# SCHEMATIC.net
KiCad netlist of a schematic drawn in EAGLE
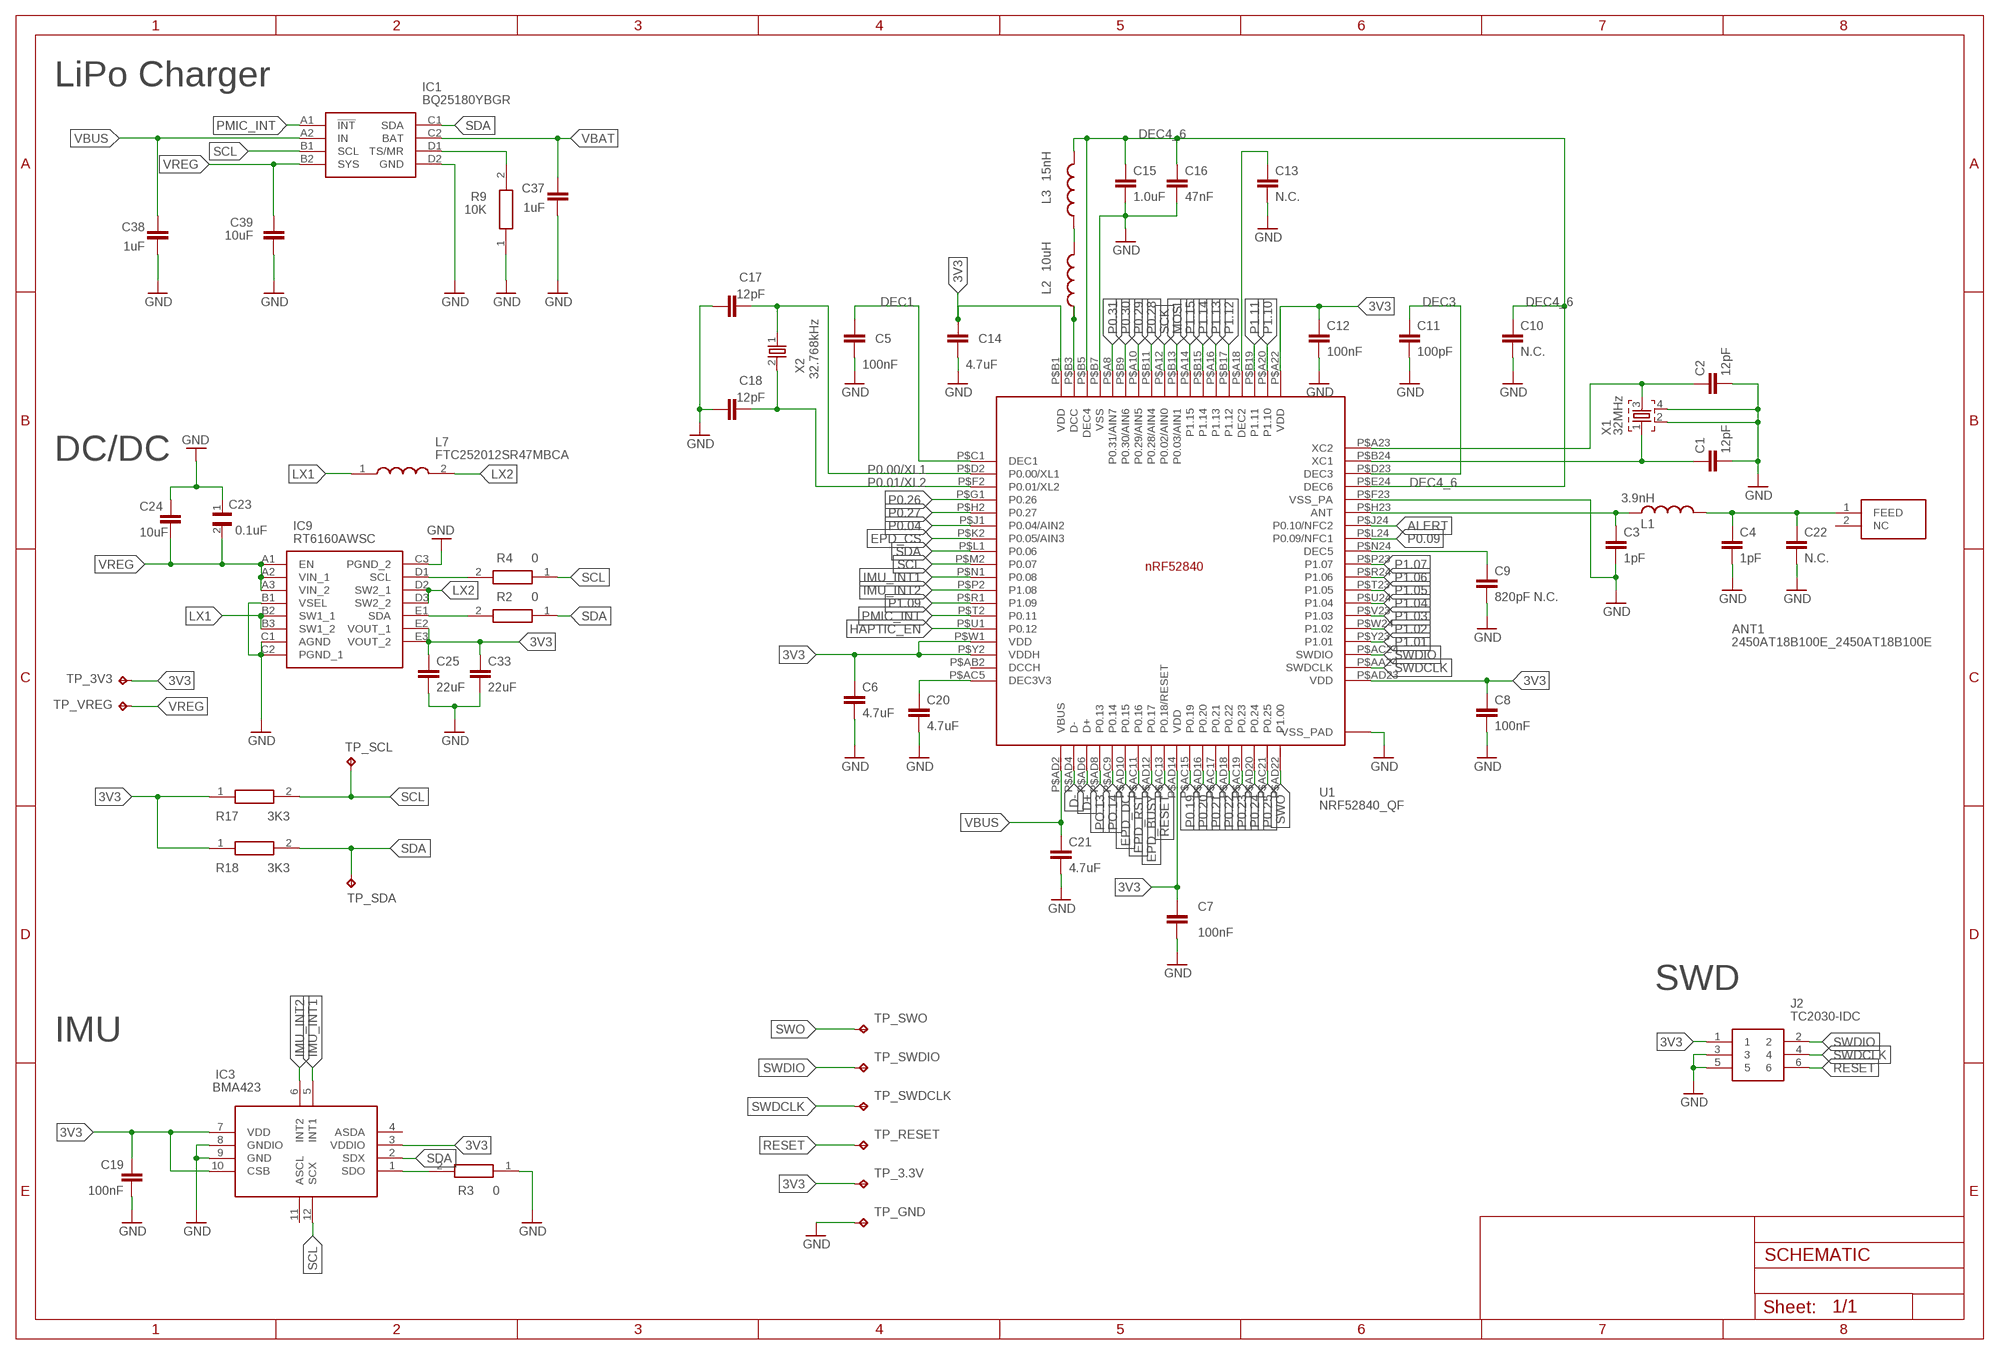
[diagram p0: schematic, sheet 1, part 1 of 2]
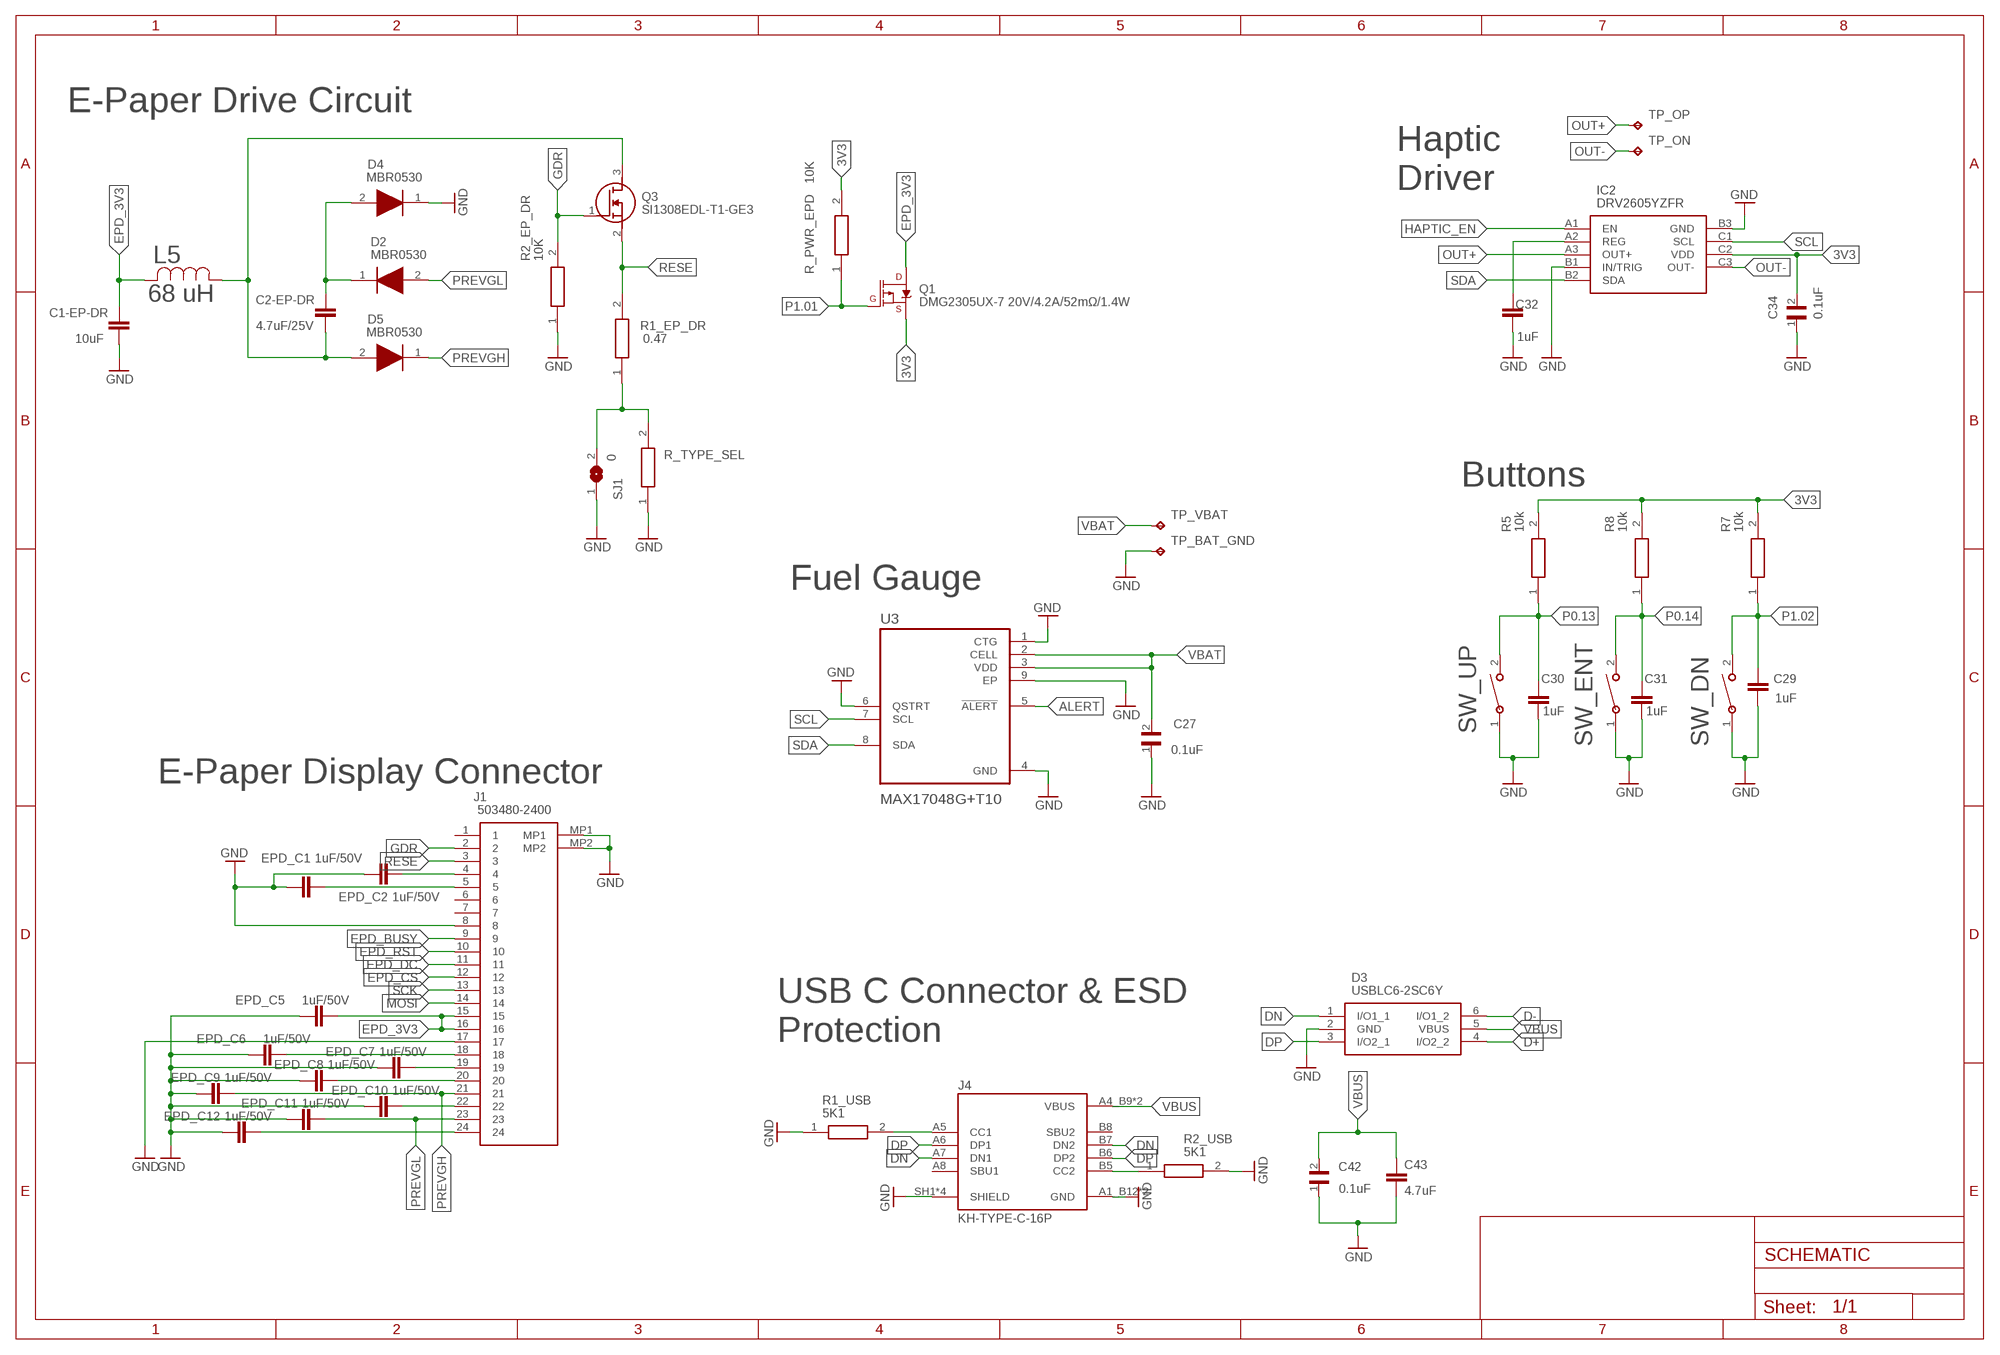
[diagram p1: schematic, sheet 1, part 2 of 2]

(export (version "E")
  (design (tool "Eeschema 10.0.6"))
  (components
    (comp (ref "ANT1")
      (value "2450AT18B100E_2450AT18B100E")
      (footprint "eagle-import:2450AT18B100E_ANTC3216X140N")
      (fields
        (field (name "ARROW_PART_NUMBER") "2450AT18B100E")
        (field (name "MOUSER_PART_NUMBER") "609-2450AT18B100E")
      )
      (libsource (lib "eagle-import") (part "2450AT18B100E_2450AT18B100E"))
    )
    (comp (ref "C1")
      (value "12pF")
      (footprint "eagle-import:NORDIC_NRF_3_RESC0201_L")
      (libsource (lib "eagle-import") (part "NORDIC_NRF_3_CAPACITOR_0201_L"))
    )
    (comp (ref "C1-EP-DR")
      (value "10uF")
      (footprint "eagle-import:PERFECT_0402_0402")
      (libsource (lib "eagle-import") (part "PERFECT_0402_CAP_0402"))
    )
    (comp (ref "C2")
      (value "12pF")
      (footprint "eagle-import:NORDIC_NRF_3_RESC0201_L")
      (libsource (lib "eagle-import") (part "NORDIC_NRF_3_CAPACITOR_0201_L"))
    )
    (comp (ref "C2-EP-DR")
      (value "4.7uF/25V")
      (footprint "eagle-import:PERFECT_0402_0402")
      (libsource (lib "eagle-import") (part "PERFECT_0402_CAP_0402"))
    )
    (comp (ref "C3")
      (value "1pF")
      (footprint "eagle-import:NORDIC_NRF_3_RESC0201_L")
      (libsource (lib "eagle-import") (part "NORDIC_NRF_3_CAPACITOR_0201_L"))
    )
    (comp (ref "C4")
      (value "1pF")
      (footprint "eagle-import:NORDIC_NRF_3_RESC0201_L")
      (libsource (lib "eagle-import") (part "NORDIC_NRF_3_CAPACITOR_0201_L"))
    )
    (comp (ref "C5")
      (value "100nF")
      (footprint "eagle-import:NORDIC_NRF_3_RESC0201_L")
      (libsource (lib "eagle-import") (part "NORDIC_NRF_3_CAPACITOR_0201_L"))
    )
    (comp (ref "C6")
      (value "4.7uF")
      (footprint "eagle-import:PERFECT_0402_0402")
      (libsource (lib "eagle-import") (part "PERFECT_0402_CAP_0402"))
    )
    (comp (ref "C7")
      (value "100nF")
      (footprint "eagle-import:NORDIC_NRF_3_RESC0201_L")
      (libsource (lib "eagle-import") (part "NORDIC_NRF_3_CAPACITOR_0201_L"))
    )
    (comp (ref "C8")
      (value "100nF")
      (footprint "eagle-import:NORDIC_NRF_3_RESC0201_L")
      (libsource (lib "eagle-import") (part "NORDIC_NRF_3_CAPACITOR_0201_L"))
    )
    (comp (ref "C9")
      (value "820pF N.C.")
      (footprint "eagle-import:NORDIC_NRF_3_RESC0201_L")
      (libsource (lib "eagle-import") (part "NORDIC_NRF_3_CAPACITOR_0201_L"))
    )
    (comp (ref "C10")
      (value "N.C.")
      (footprint "eagle-import:NORDIC_NRF_3_RESC0201_L")
      (libsource (lib "eagle-import") (part "NORDIC_NRF_3_CAPACITOR_0201_L"))
    )
    (comp (ref "C11")
      (value "100pF")
      (footprint "eagle-import:NORDIC_NRF_3_RESC0201_L")
      (libsource (lib "eagle-import") (part "NORDIC_NRF_3_CAPACITOR_0201_L"))
    )
    (comp (ref "C12")
      (value "100nF")
      (footprint "eagle-import:NORDIC_NRF_3_RESC0201_L")
      (libsource (lib "eagle-import") (part "NORDIC_NRF_3_CAPACITOR_0201_L"))
    )
    (comp (ref "C13")
      (value "N.C.")
      (footprint "eagle-import:NORDIC_NRF_3_RESC0201_L")
      (libsource (lib "eagle-import") (part "NORDIC_NRF_3_CAPACITOR_0201_L"))
    )
    (comp (ref "C14")
      (value "4.7uF")
      (footprint "eagle-import:PERFECT_0402_0402")
      (libsource (lib "eagle-import") (part "PERFECT_0402_CAP_0402"))
    )
    (comp (ref "C15")
      (value "1.0uF")
      (footprint "eagle-import:PERFECT_0402_0402")
      (libsource (lib "eagle-import") (part "PERFECT_0402_CAP_0402"))
    )
    (comp (ref "C16")
      (value "47nF")
      (footprint "eagle-import:NORDIC_NRF_3_RESC0201_L")
      (libsource (lib "eagle-import") (part "NORDIC_NRF_3_CAPACITOR_0201_L"))
    )
    (comp (ref "C17")
      (value "12pF")
      (footprint "eagle-import:NORDIC_NRF_3_RESC0201_L")
      (libsource (lib "eagle-import") (part "NORDIC_NRF_3_CAPACITOR_0201_L"))
    )
    (comp (ref "C18")
      (value "12pF")
      (footprint "eagle-import:NORDIC_NRF_3_RESC0201_L")
      (libsource (lib "eagle-import") (part "NORDIC_NRF_3_CAPACITOR_0201_L"))
    )
    (comp (ref "C19")
      (value "100nF")
      (footprint "eagle-import:NORDIC_NRF_3_RESC0201_L")
      (libsource (lib "eagle-import") (part "NORDIC_NRF_3_CAPACITOR_0201_L"))
    )
    (comp (ref "C20")
      (value "4.7uF")
      (footprint "eagle-import:PERFECT_0402_0402")
      (libsource (lib "eagle-import") (part "PERFECT_0402_CAP_0402"))
    )
    (comp (ref "C21")
      (value "4.7uF")
      (footprint "eagle-import:PERFECT_0402_0402")
      (libsource (lib "eagle-import") (part "PERFECT_0402_CAP_0402"))
    )
    (comp (ref "C22")
      (value "N.C.")
      (footprint "eagle-import:NORDIC_NRF_3_RESC0201_L")
      (libsource (lib "eagle-import") (part "NORDIC_NRF_3_CAPACITOR_0201_L"))
    )
    (comp (ref "C23")
      (value "0.1uF")
      (footprint "eagle-import:GRM011R60J152KE01L_1_0201")
      (libsource (lib "eagle-import") (part "GRM011R60J152KE01L_1_GRM011R60J152KE01L"))
    )
    (comp (ref "C24")
      (value "10uF")
      (footprint "eagle-import:PERFECT_0402_0402")
      (libsource (lib "eagle-import") (part "PERFECT_0402_CAP_0402"))
    )
    (comp (ref "C25")
      (value "22uF")
      (footprint "eagle-import:PERFECT_0402_0402")
      (libsource (lib "eagle-import") (part "PERFECT_0402_CAP_0402"))
    )
    (comp (ref "C27")
      (value "0.1uF")
      (footprint "eagle-import:GRM011R60J152KE01L_2_CAPC0201X13N")
      (fields (field (name "MF") "Murata") (field (name "MP") "GRM011R60J152KE01L"))
      (libsource (lib "eagle-import") (part "GRM011R60J152KE01L_2_GRM011R60J152KE01L"))
    )
    (comp (ref "C29")
      (value "1uF")
      (footprint "eagle-import:NORDIC_NRF_3_RESC0402_L")
      (libsource (lib "eagle-import") (part "NORDIC_NRF_3_CAPACITOR_0402_L"))
    )
    (comp (ref "C30")
      (value "1uF")
      (footprint "eagle-import:NORDIC_NRF_3_RESC0402_L")
      (libsource (lib "eagle-import") (part "NORDIC_NRF_3_CAPACITOR_0402_L"))
    )
    (comp (ref "C31")
      (value "1uF")
      (footprint "eagle-import:NORDIC_NRF_3_RESC0402_L")
      (libsource (lib "eagle-import") (part "NORDIC_NRF_3_CAPACITOR_0402_L"))
    )
    (comp (ref "C32")
      (value "1uF")
      (footprint "eagle-import:NORDIC_NRF_3_RESC0402_L")
      (libsource (lib "eagle-import") (part "NORDIC_NRF_3_CAPACITOR_0402_L"))
    )
    (comp (ref "C33")
      (value "22uF")
      (footprint "eagle-import:PERFECT_0402_0402")
      (libsource (lib "eagle-import") (part "PERFECT_0402_CAP_0402"))
    )
    (comp (ref "C34")
      (value "0.1uF")
      (footprint "eagle-import:GRM011R60J152KE01L_2_CAPC0201X13N")
      (fields (field (name "MF") "Murata") (field (name "MP") "GRM011R60J152KE01L"))
      (libsource (lib "eagle-import") (part "GRM011R60J152KE01L_2_GRM011R60J152KE01L"))
    )
    (comp (ref "C37")
      (value "1uF")
      (footprint "eagle-import:NORDIC_NRF_3_RESC0402_L")
      (libsource (lib "eagle-import") (part "NORDIC_NRF_3_CAPACITOR_0402_L"))
    )
    (comp (ref "C38")
      (value "1uF")
      (footprint "eagle-import:NORDIC_NRF_3_RESC0402_L")
      (libsource (lib "eagle-import") (part "NORDIC_NRF_3_CAPACITOR_0402_L"))
    )
    (comp (ref "C39")
      (value "10uF")
      (footprint "eagle-import:NORDIC_NRF_3_RESC0402_L")
      (libsource (lib "eagle-import") (part "NORDIC_NRF_3_CAPACITOR_0402_L"))
    )
    (comp (ref "C42")
      (value "0.1uF")
      (footprint "eagle-import:GRM011R60J152KE01L_2_CAPC0201X13N")
      (fields (field (name "MF") "Murata") (field (name "MP") "GRM011R60J152KE01L"))
      (libsource (lib "eagle-import") (part "GRM011R60J152KE01L_2_GRM011R60J152KE01L"))
    )
    (comp (ref "C43")
      (value "4.7uF")
      (footprint "eagle-import:PERFECT_0402_0402")
      (libsource (lib "eagle-import") (part "PERFECT_0402_CAP_0402"))
    )
    (comp (ref "D2")
      (value "MBR0530")
      (footprint "eagle-import:ESP32_C6_LIBRARY_5_SOD3716X135N")
      (fields (field (name "MF") "ON Semiconductor"))
      (libsource (lib "eagle-import") (part "ESP32_C6_LIBRARY_5_MBR0530"))
    )
    (comp (ref "D3")
      (value "USBLC6-2SC6Y")
      (footprint "eagle-import:ESP32_C6_LIBRARY_3_SOT95P280X145-6N")
      (fields (field (name "MF") "STMicroelectronics"))
      (libsource (lib "eagle-import") (part "ESP32_C6_LIBRARY_3_USBLC6-2SC6Y"))
    )
    (comp (ref "D4")
      (value "MBR0530")
      (footprint "eagle-import:ESP32_C6_LIBRARY_5_SOD3716X135N")
      (fields (field (name "MF") "ON Semiconductor"))
      (libsource (lib "eagle-import") (part "ESP32_C6_LIBRARY_5_MBR0530"))
    )
    (comp (ref "D5")
      (value "MBR0530")
      (footprint "eagle-import:ESP32_C6_LIBRARY_5_SOD3716X135N")
      (fields (field (name "MF") "ON Semiconductor"))
      (libsource (lib "eagle-import") (part "ESP32_C6_LIBRARY_5_MBR0530"))
    )
    (comp (ref "EPD_C1")
      (value "1uF/50V")
      (footprint "eagle-import:PERFECT_0402_0402")
      (libsource (lib "eagle-import") (part "PERFECT_0402_CAP_0402"))
    )
    (comp (ref "EPD_C2")
      (value "1uF/50V")
      (footprint "eagle-import:PERFECT_0402_0402")
      (libsource (lib "eagle-import") (part "PERFECT_0402_CAP_0402"))
    )
    (comp (ref "EPD_C5")
      (value "1uF/50V")
      (footprint "eagle-import:PERFECT_0402_0402")
      (libsource (lib "eagle-import") (part "PERFECT_0402_CAP_0402"))
    )
    (comp (ref "EPD_C6")
      (value "1uF/50V")
      (footprint "eagle-import:PERFECT_0402_0402")
      (libsource (lib "eagle-import") (part "PERFECT_0402_CAP_0402"))
    )
    (comp (ref "EPD_C7")
      (value "1uF/50V")
      (footprint "eagle-import:PERFECT_0402_0402")
      (libsource (lib "eagle-import") (part "PERFECT_0402_CAP_0402"))
    )
    (comp (ref "EPD_C8")
      (value "1uF/50V")
      (footprint "eagle-import:PERFECT_0402_0402")
      (libsource (lib "eagle-import") (part "PERFECT_0402_CAP_0402"))
    )
    (comp (ref "EPD_C9")
      (value "1uF/50V")
      (footprint "eagle-import:PERFECT_0402_0402")
      (libsource (lib "eagle-import") (part "PERFECT_0402_CAP_0402"))
    )
    (comp (ref "EPD_C10")
      (value "1uF/50V")
      (footprint "eagle-import:PERFECT_0402_0402")
      (libsource (lib "eagle-import") (part "PERFECT_0402_CAP_0402"))
    )
    (comp (ref "EPD_C11")
      (value "1uF/50V")
      (footprint "eagle-import:PERFECT_0402_0402")
      (libsource (lib "eagle-import") (part "PERFECT_0402_CAP_0402"))
    )
    (comp (ref "EPD_C12")
      (value "1uF/50V")
      (footprint "eagle-import:PERFECT_0402_0402")
      (libsource (lib "eagle-import") (part "PERFECT_0402_CAP_0402"))
    )
    (comp (ref "IC1")
      (value "BQ25180YBGR")
      (footprint "eagle-import:BQ25180YBGR_BGA8C40P2X4_100X155X50")
      (fields (field (name "MOUSER_PART_NUMBER") "595-BQ25180YBGR"))
      (libsource (lib "eagle-import") (part "BQ25180YBGR_BQ25180YBGR"))
    )
    (comp (ref "IC2")
      (value "DRV2605YZFR")
      (footprint "eagle-import:DRV2605YZFR_BGA9C50P3X3_144X144X62")
      (libsource (lib "eagle-import") (part "DRV2605YZFR_DRV2605YZFR"))
    )
    (comp (ref "IC3")
      (value "BMA423")
      (footprint "eagle-import:BMA423_BMA423")
      (fields (field (name "MOUSER_PART_NUMBER") "262-BMA423"))
      (libsource (lib "eagle-import") (part "BMA423_BMA423"))
    )
    (comp (ref "IC9")
      (value "RT6160AWSC")
      (footprint "eagle-import:RT6160AWSC_BGA15C40P3X5_140X230X60")
      (fields (field (name "MOUSER_PART_NUMBER") "835-RT6160AWSC"))
      (libsource (lib "eagle-import") (part "RT6160AWSC_RT6160AWSC"))
    )
    (comp (ref "J1")
      (value "503480-2400")
      (footprint "eagle-import:503480-2400_5034802400")
      (fields (field (name "MOUSER_PART_NUMBER") "538-503480-2400"))
      (libsource (lib "eagle-import") (part "503480-2400_503480-2400"))
    )
    (comp (ref "J2")
      (value "TC2030-IDC")
      (footprint "eagle-import:TC2030-IDC_TC2030IDC")
      (libsource (lib "eagle-import") (part "TC2030-IDC_TC2030-IDC"))
    )
    (comp (ref "J4")
      (value "KH-TYPE-C-16P")
      (footprint "eagle-import:KH-TYPE-C-16P_KINGHELM_KH-TYPE-C-16P")
      (fields (field (name "MF") "kinghelm"))
      (libsource (lib "eagle-import") (part "KH-TYPE-C-16P_KH-TYPE-C-16P"))
    )
    (comp (ref "L1")
      (value "3.9nH")
      (footprint "eagle-import:NORDIC_NRF_2_RESC0402_L")
      (libsource (lib "eagle-import") (part "NORDIC_NRF_2_INDUCTOR_0402_L"))
    )
    (comp (ref "L2")
      (value "10uH")
      (footprint "eagle-import:NORDIC_NRF_2_RESC0402_L")
      (libsource (lib "eagle-import") (part "NORDIC_NRF_2_INDUCTOR_0402_L"))
    )
    (comp (ref "L3")
      (value "15nH")
      (footprint "eagle-import:NORDIC_NRF_2_RESC0402_L")
      (libsource (lib "eagle-import") (part "NORDIC_NRF_2_INDUCTOR_0402_L"))
    )
    (comp (ref "L5")
      (value "68 uH")
      (footprint "eagle-import:ESP32_C6_LIBRARY_2_IND_4828-WE-TPC_WRE")
      (fields
        (field (name "MANUFACTURER_PART_NUMBER") "744043680")
        (field (name "COPYRIGHT") "Copyright (C) 2024 Ultra Librarian. All rights reserved.")
      )
      (libsource (lib "eagle-import") (part "ESP32_C6_LIBRARY_2_744043680IND_4828-WE-TPC_WRE"))
    )
    (comp (ref "L7")
      (value "FTC252012SR47MBCA")
      (footprint "eagle-import:MLP2016SR47MT0S1_INDC2016X100N")
      (libsource (lib "eagle-import") (part "MLP2016SR47MT0S1_FTC252012SR47MBCA"))
    )
    (comp (ref "Q1")
      (value "DMG2305UX-7 20V/4.2A/52mΩ/1.4W")
      (footprint "eagle-import:ESP32_C6_LIBRARY_4_ESP32_C6_LIBRARY_4_ESP32_C6_LIBRARY_4_ESP32_C6_LIBRARY_4_ESP32_WROVER_SPARKFUN-DISCRETESEMI_SOT23-3")
      (libsource (lib "eagle-import") (part "ESP32_C6_LIBRARY_4_ESP32_WROVER_SPARKFUN-DISCRETESEMI_MOSFET_PCH-DMG2305UX-7"))
    )
    (comp (ref "Q3")
      (value "SI1308EDL-T1-GE3")
      (footprint "eagle-import:ESP32_C6_LIBRARY_6_SOT65P210X110-3N")
      (fields (field (name "MF") "Vishay Siliconix"))
      (libsource (lib "eagle-import") (part "ESP32_C6_LIBRARY_6_SI1308EDL-T1-GE3"))
    )
    (comp (ref "R1_EP_DR")
      (value "0.47")
      (footprint "eagle-import:ERA-1AEB3401C_0201")
      (libsource (lib "eagle-import") (part "ERA-1AEB3401C_CPF0201D7K68C1"))
    )
    (comp (ref "R1_USB")
      (value "5K1")
      (footprint "eagle-import:CPF0201D7K68C1_0201")
      (libsource (lib "eagle-import") (part "CPF0201D7K68C1_CPF0201D7K68C1"))
    )
    (comp (ref "R2")
      (value "0")
      (footprint "eagle-import:ERA-1AEB3401C_0201")
      (libsource (lib "eagle-import") (part "ERA-1AEB3401C_CPF0201D7K68C1"))
    )
    (comp (ref "R2_EP_DR")
      (value "10K")
      (footprint "eagle-import:ERA-1AEB3401C_0201")
      (libsource (lib "eagle-import") (part "ERA-1AEB3401C_CPF0201D7K68C1"))
    )
    (comp (ref "R2_USB")
      (value "5K1")
      (footprint "eagle-import:CPF0201D7K68C1_0201")
      (libsource (lib "eagle-import") (part "CPF0201D7K68C1_CPF0201D7K68C1"))
    )
    (comp (ref "R3")
      (value "0")
      (footprint "eagle-import:CPF0201D7K68C1_0201")
      (libsource (lib "eagle-import") (part "CPF0201D7K68C1_CPF0201D7K68C1"))
    )
    (comp (ref "R4")
      (value "0")
      (footprint "eagle-import:ERA-1AEB3401C_0201")
      (libsource (lib "eagle-import") (part "ERA-1AEB3401C_CPF0201D7K68C1"))
    )
    (comp (ref "R5")
      (value "10k")
      (footprint "eagle-import:CPF0201D7K68C1_0201")
      (libsource (lib "eagle-import") (part "CPF0201D7K68C1_CPF0201D7K68C1"))
    )
    (comp (ref "R7")
      (value "10k")
      (footprint "eagle-import:CPF0201D7K68C1_0201")
      (libsource (lib "eagle-import") (part "CPF0201D7K68C1_CPF0201D7K68C1"))
    )
    (comp (ref "R8")
      (value "10k")
      (footprint "eagle-import:CPF0201D7K68C1_0201")
      (libsource (lib "eagle-import") (part "CPF0201D7K68C1_CPF0201D7K68C1"))
    )
    (comp (ref "R9")
      (value "10K")
      (footprint "eagle-import:ERA-1AEB3401C_0201")
      (libsource (lib "eagle-import") (part "ERA-1AEB3401C_CPF0201D7K68C1"))
    )
    (comp (ref "R17")
      (value "3K3")
      (footprint "eagle-import:ERA-1AEB3401C_0201")
      (libsource (lib "eagle-import") (part "ERA-1AEB3401C_CPF0201D7K68C1"))
    )
    (comp (ref "R18")
      (value "3K3")
      (footprint "eagle-import:ERA-1AEB3401C_0201")
      (libsource (lib "eagle-import") (part "ERA-1AEB3401C_CPF0201D7K68C1"))
    )
    (comp (ref "R_PWR_EPD")
      (value "10K")
      (footprint "eagle-import:CPF0201D7K68C1_0201")
      (libsource (lib "eagle-import") (part "CPF0201D7K68C1_CPF0201D7K68C1"))
    )
    (comp (ref "R_TYPE_SEL")
      (value "2.2")
      (footprint "eagle-import:ERA-1AEB3401C_0201")
      (libsource (lib "eagle-import") (part "ERA-1AEB3401C_CPF0201D7K68C1"))
    )
    (comp (ref "SJ1")
      (value "0")
      (footprint "eagle-import:ESP32_C6_LIBRARY_7_JUMPER_SJ")
      (libsource (lib "eagle-import") (part "ESP32_C6_LIBRARY_7_JUMPER_SJ"))
    )
    (comp (ref "SW_DN")
      (value "2025-10-22_07-23-44_LIBRARY_EVP-AKE31ASW_EVP-AKE31A_PAN")
      (footprint "eagle-import:2025-10-22_07-23-44_LIBRARY_SW_EVP-AKE31A_PAN")
      (fields
        (field (name "MANUFACTURER_PART_NUMBER") "EVP-AKE31A")
        (field (name "COPYRIGHT") "Copyright (C) 2025 Ultra Librarian. All rights reserved.")
      )
      (libsource (lib "eagle-import") (part "2025-10-22_07-23-44_LIBRARY_EVP-AKE31ASW_EVP-AKE31A_PAN"))
    )
    (comp (ref "SW_ENT")
      (value "2025-10-22_07-23-44_LIBRARY_EVP-AKE31ASW_EVP-AKE31A_PAN")
      (footprint "eagle-import:2025-10-22_07-23-44_LIBRARY_SW_EVP-AKE31A_PAN")
      (fields
        (field (name "MANUFACTURER_PART_NUMBER") "EVP-AKE31A")
        (field (name "COPYRIGHT") "Copyright (C) 2025 Ultra Librarian. All rights reserved.")
      )
      (libsource (lib "eagle-import") (part "2025-10-22_07-23-44_LIBRARY_EVP-AKE31ASW_EVP-AKE31A_PAN"))
    )
    (comp (ref "SW_UP")
      (value "2025-10-22_07-23-44_LIBRARY_EVP-AKE31ASW_EVP-AKE31A_PAN")
      (footprint "eagle-import:2025-10-22_07-23-44_LIBRARY_SW_EVP-AKE31A_PAN")
      (fields
        (field (name "MANUFACTURER_PART_NUMBER") "EVP-AKE31A")
        (field (name "COPYRIGHT") "Copyright (C) 2025 Ultra Librarian. All rights reserved.")
      )
      (libsource (lib "eagle-import") (part "2025-10-22_07-23-44_LIBRARY_EVP-AKE31ASW_EVP-AKE31A_PAN"))
    )
    (comp (ref "TP_3.3V")
      (value "HECTOR_WATCH_1_TPTP20R")
      (footprint "eagle-import:HECTOR_WATCH_1_TP20R")
      (libsource (lib "eagle-import") (part "HECTOR_WATCH_1_TPTP20R"))
    )
    (comp (ref "TP_3V3")
      (value "HECTOR_WATCH_1_TPTP20R")
      (footprint "eagle-import:HECTOR_WATCH_1_TP20R")
      (libsource (lib "eagle-import") (part "HECTOR_WATCH_1_TPTP20R"))
    )
    (comp (ref "TP_BAT_GND")
      (value "HECTOR_WATCH_1_TPTP20R")
      (footprint "eagle-import:HECTOR_WATCH_1_TP20R")
      (libsource (lib "eagle-import") (part "HECTOR_WATCH_1_TPTP20R"))
    )
    (comp (ref "TP_GND")
      (value "HECTOR_WATCH_1_TPTP20R")
      (footprint "eagle-import:HECTOR_WATCH_1_TP20R")
      (libsource (lib "eagle-import") (part "HECTOR_WATCH_1_TPTP20R"))
    )
    (comp (ref "TP_ON")
      (value "HECTOR_WATCH_1_TPTP20R")
      (footprint "eagle-import:HECTOR_WATCH_1_TP20R")
      (libsource (lib "eagle-import") (part "HECTOR_WATCH_1_TPTP20R"))
    )
    (comp (ref "TP_OP")
      (value "HECTOR_WATCH_1_TPTP20R")
      (footprint "eagle-import:HECTOR_WATCH_1_TP20R")
      (libsource (lib "eagle-import") (part "HECTOR_WATCH_1_TPTP20R"))
    )
    (comp (ref "TP_RESET")
      (value "HECTOR_WATCH_1_TPTP20R")
      (footprint "eagle-import:HECTOR_WATCH_1_TP20R")
      (libsource (lib "eagle-import") (part "HECTOR_WATCH_1_TPTP20R"))
    )
    (comp (ref "TP_SCL")
      (value "HECTOR_WATCH_1_TPTP20R")
      (footprint "eagle-import:HECTOR_WATCH_1_TP20R")
      (libsource (lib "eagle-import") (part "HECTOR_WATCH_1_TPTP20R"))
    )
    (comp (ref "TP_SDA")
      (value "HECTOR_WATCH_1_TPTP20R")
      (footprint "eagle-import:HECTOR_WATCH_1_TP20R")
      (libsource (lib "eagle-import") (part "HECTOR_WATCH_1_TPTP20R"))
    )
    (comp (ref "TP_SWDCLK")
      (value "HECTOR_WATCH_1_TPTP20R")
      (footprint "eagle-import:HECTOR_WATCH_1_TP20R")
      (libsource (lib "eagle-import") (part "HECTOR_WATCH_1_TPTP20R"))
    )
    (comp (ref "TP_SWDIO")
      (value "HECTOR_WATCH_1_TPTP20R")
      (footprint "eagle-import:HECTOR_WATCH_1_TP20R")
      (libsource (lib "eagle-import") (part "HECTOR_WATCH_1_TPTP20R"))
    )
    (comp (ref "TP_SWO")
      (value "HECTOR_WATCH_1_TPTP20R")
      (footprint "eagle-import:HECTOR_WATCH_1_TP20R")
      (libsource (lib "eagle-import") (part "HECTOR_WATCH_1_TPTP20R"))
    )
    (comp (ref "TP_VBAT")
      (value "HECTOR_WATCH_1_TPTP20R")
      (footprint "eagle-import:HECTOR_WATCH_1_TP20R")
      (libsource (lib "eagle-import") (part "HECTOR_WATCH_1_TPTP20R"))
    )
    (comp (ref "TP_VREG")
      (value "HECTOR_WATCH_1_TPTP20R")
      (footprint "eagle-import:HECTOR_WATCH_1_TP20R")
      (libsource (lib "eagle-import") (part "HECTOR_WATCH_1_TPTP20R"))
    )
    (comp (ref "U1")
      (value "NRF52840_QF")
      (footprint "eagle-import:NORDIC_NRF_4_AQFN50P700X700X85_HS-74N")
      (libsource (lib "eagle-import") (part "NORDIC_NRF_4_NRF52840_QF"))
    )
    (comp (ref "U3")
      (value "MAX17048G+T10")
      (footprint "eagle-import:ESP32_C6_LIBRARY_SON50P200X200X80-9N")
      (fields (field (name "MF") "Analog Devices"))
      (libsource (lib "eagle-import") (part "ESP32_C6_LIBRARY_MAX17048G+T10"))
    )
    (comp (ref "X1")
      (value "32MHz")
      (footprint "eagle-import:NORDIC_NRF_BT-XTAL_2016_N")
      (libsource (lib "eagle-import") (part "NORDIC_NRF_XTAL_32MHZ"))
    )
    (comp (ref "X2")
      (value "32.768kHz")
      (footprint "eagle-import:NORDIC_NRF_1_XTAL_3215_N")
      (libsource (lib "eagle-import") (part "NORDIC_NRF_1_XTAL_32KHZ"))
    )
  )
  (nets
    (net (code "1") (name "/DEC1") (class "Default")
      (node (ref "C5") (pin "1") (pinfunction "1_1") (pintype "passive"))
      (node (ref "U1") (pin "P$C1") (pinfunction "DEC1_P$C1") (pintype "power_in"))
    )
    (net (code "2") (name "/DEC3") (class "Default")
      (node (ref "C11") (pin "1") (pinfunction "1_1") (pintype "passive"))
      (node (ref "U1") (pin "P$D23") (pinfunction "DEC3_P$D23") (pintype "bidirectional"))
    )
    (net (code "3") (name "/DEC4_6") (class "Default")
      (node (ref "C10") (pin "1") (pinfunction "1_1") (pintype "passive"))
      (node (ref "C15") (pin "1") (pinfunction "1_1") (pintype "passive"))
      (node (ref "C16") (pin "1") (pinfunction "1_1") (pintype "passive"))
      (node (ref "L3") (pin "2") (pinfunction "2_2") (pintype "passive"))
      (node (ref "U1") (pin "P$B5") (pinfunction "DEC4_P$B5") (pintype "power_in"))
      (node (ref "U1") (pin "P$E24") (pinfunction "DEC6_P$E24") (pintype "bidirectional"))
    )
    (net (code "4") (name "/P0.00{slash}XL1") (class "Default")
      (node (ref "C17") (pin "2") (pinfunction "2_2") (pintype "passive"))
      (node (ref "U1") (pin "P$D2") (pinfunction "P0.00/XL1_P$D2") (pintype "bidirectional"))
      (node (ref "X2") (pin "1") (pinfunction "1_1") (pintype "passive"))
    )
    (net (code "5") (name "/P0.01{slash}XL2") (class "Default")
      (node (ref "C18") (pin "2") (pinfunction "2_2") (pintype "passive"))
      (node (ref "U1") (pin "P$F2") (pinfunction "P0.01/XL2_P$F2") (pintype "bidirectional"))
      (node (ref "X2") (pin "2") (pinfunction "2_2") (pintype "passive"))
    )
    (net (code "6") (name "3V3") (class "Default")
      (node (ref "C12") (pin "1") (pinfunction "1_1") (pintype "passive"))
      (node (ref "C14") (pin "1") (pinfunction "1_1") (pintype "passive"))
      (node (ref "C19") (pin "1") (pinfunction "1_1") (pintype "passive"))
      (node (ref "C25") (pin "1") (pinfunction "1_1") (pintype "passive"))
      (node (ref "C33") (pin "1") (pinfunction "1_1") (pintype "passive"))
      (node (ref "C34") (pin "2") (pinfunction "2_2") (pintype "passive"))
      (node (ref "C6") (pin "1") (pinfunction "1_1") (pintype "passive"))
      (node (ref "C7") (pin "1") (pinfunction "1_1") (pintype "passive"))
      (node (ref "C8") (pin "1") (pinfunction "1_1") (pintype "passive"))
      (node (ref "IC2") (pin "C2") (pinfunction "VDD_C2") (pintype "bidirectional"))
      (node (ref "IC3") (pin "10") (pinfunction "CSB_10") (pintype "bidirectional"))
      (node (ref "IC3") (pin "3") (pinfunction "VDDIO_3") (pintype "bidirectional"))
      (node (ref "IC3") (pin "7") (pinfunction "VDD_7") (pintype "bidirectional"))
      (node (ref "IC9") (pin "E2") (pinfunction "VOUT_1_E2") (pintype "bidirectional"))
      (node (ref "IC9") (pin "E3") (pinfunction "VOUT_2_E3") (pintype "bidirectional"))
      (node (ref "J2") (pin "1") (pinfunction "1_1") (pintype "bidirectional"))
      (node (ref "Q1") (pin "2") (pinfunction "S_2") (pintype "bidirectional"))
      (node (ref "R17") (pin "1") (pinfunction "1_1") (pintype "bidirectional"))
      (node (ref "R18") (pin "1") (pinfunction "1_1") (pintype "bidirectional"))
      (node (ref "R5") (pin "2") (pinfunction "2_2") (pintype "bidirectional"))
      (node (ref "R7") (pin "2") (pinfunction "2_2") (pintype "bidirectional"))
      (node (ref "R8") (pin "2") (pinfunction "2_2") (pintype "bidirectional"))
      (node (ref "R_PWR_EPD") (pin "2") (pinfunction "2_2") (pintype "bidirectional"))
      (node (ref "TP_3.3V") (pin "TP") (pinfunction "TP_TP") (pintype "input"))
      (node (ref "TP_3V3") (pin "TP") (pinfunction "TP_TP") (pintype "input"))
      (node (ref "U1") (pin "P$A22") (pinfunction "VDD_P$A22") (pintype "power_in"))
      (node (ref "U1") (pin "P$AD14") (pinfunction "VDD_P$AD14") (pintype "power_in"))
      (node (ref "U1") (pin "P$AD23") (pinfunction "VDD_P$AD23") (pintype "power_in"))
      (node (ref "U1") (pin "P$B1") (pinfunction "VDD_P$B1") (pintype "power_in"))
      (node (ref "U1") (pin "P$W1") (pinfunction "VDD_P$W1") (pintype "power_in"))
      (node (ref "U1") (pin "P$Y2") (pinfunction "VDDH_P$Y2") (pintype "power_in"))
    )
    (net (code "7") (name "ALERT") (class "Default")
      (node (ref "U1") (pin "P$J24") (pinfunction "P0.10/NFC2_P$J24") (pintype "bidirectional"))
      (node (ref "U3") (pin "5") (pinfunction "~{ALERT}_5") (pintype "output"))
    )
    (net (code "8") (name "D+") (class "Default")
      (node (ref "D3") (pin "4") (pinfunction "I/O2_2_4") (pintype "bidirectional"))
      (node (ref "U1") (pin "P$AD6") (pinfunction "D+_P$AD6") (pintype "bidirectional"))
    )
    (net (code "9") (name "D-") (class "Default")
      (node (ref "D3") (pin "6") (pinfunction "I/O1_2_6") (pintype "bidirectional"))
      (node (ref "U1") (pin "P$AD4") (pinfunction "D-_P$AD4") (pintype "bidirectional"))
    )
    (net (code "10") (name "DN") (class "Default")
      (node (ref "D3") (pin "1") (pinfunction "I/O1_1_1") (pintype "bidirectional"))
      (node (ref "J4") (pin "A7") (pinfunction "DN1_A7") (pintype "bidirectional"))
      (node (ref "J4") (pin "B7") (pinfunction "DN2_B7") (pintype "bidirectional"))
    )
    (net (code "11") (name "DP") (class "Default")
      (node (ref "D3") (pin "3") (pinfunction "I/O2_1_3") (pintype "bidirectional"))
      (node (ref "J4") (pin "A6") (pinfunction "DP1_A6") (pintype "bidirectional"))
      (node (ref "J4") (pin "B6") (pinfunction "DP2_B6") (pintype "bidirectional"))
    )
    (net (code "12") (name "EPD_3V3") (class "Default")
      (node (ref "C1-EP-DR") (pin "1") (pinfunction "1_1") (pintype "passive"))
      (node (ref "EPD_C5") (pin "2") (pinfunction "2_2") (pintype "passive"))
      (node (ref "J1") (pin "15") (pinfunction "15_15") (pintype "bidirectional"))
      (node (ref "J1") (pin "16") (pinfunction "16_16") (pintype "bidirectional"))
      (node (ref "L5") (pin "2") (pinfunction "2_2") (pintype "passive"))
      (node (ref "Q1") (pin "3") (pinfunction "D_3") (pintype "bidirectional"))
    )
    (net (code "13") (name "EPD_BUSY") (class "Default")
      (node (ref "J1") (pin "9") (pinfunction "9_9") (pintype "bidirectional"))
      (node (ref "U1") (pin "P$AD12") (pinfunction "P0.17_P$AD12") (pintype "bidirectional"))
    )
    (net (code "14") (name "EPD_CS") (class "Default")
      (node (ref "J1") (pin "12") (pinfunction "12_12") (pintype "bidirectional"))
      (node (ref "U1") (pin "P$K2") (pinfunction "P0.05/AIN3_P$K2") (pintype "bidirectional"))
    )
    (net (code "15") (name "EPD_DC") (class "Default")
      (node (ref "J1") (pin "11") (pinfunction "11_11") (pintype "bidirectional"))
      (node (ref "U1") (pin "P$AD10") (pinfunction "P0.15_P$AD10") (pintype "bidirectional"))
    )
    (net (code "16") (name "EPD_RST") (class "Default")
      (node (ref "J1") (pin "10") (pinfunction "10_10") (pintype "bidirectional"))
      (node (ref "U1") (pin "P$AC11") (pinfunction "P0.16_P$AC11") (pintype "bidirectional"))
    )
    (net (code "17") (name "GDR") (class "Default")
      (node (ref "J1") (pin "2") (pinfunction "2_2") (pintype "bidirectional"))
      (node (ref "Q3") (pin "1") (pinfunction "G_1") (pintype "bidirectional"))
      (node (ref "R2_EP_DR") (pin "2") (pinfunction "2_2") (pintype "bidirectional"))
    )
    (net (code "18") (name "GND") (class "Default")
      (node (ref "C1") (pin "2") (pinfunction "2_2") (pintype "passive"))
      (node (ref "C1-EP-DR") (pin "2") (pinfunction "2_2") (pintype "passive"))
      (node (ref "C10") (pin "2") (pinfunction "2_2") (pintype "passive"))
      (node (ref "C11") (pin "2") (pinfunction "2_2") (pintype "passive"))
      (node (ref "C12") (pin "2") (pinfunction "2_2") (pintype "passive"))
      (node (ref "C13") (pin "2") (pinfunction "2_2") (pintype "passive"))
      (node (ref "C14") (pin "2") (pinfunction "2_2") (pintype "passive"))
      (node (ref "C15") (pin "2") (pinfunction "2_2") (pintype "passive"))
      (node (ref "C16") (pin "2") (pinfunction "2_2") (pintype "passive"))
      (node (ref "C17") (pin "1") (pinfunction "1_1") (pintype "passive"))
      (node (ref "C18") (pin "1") (pinfunction "1_1") (pintype "passive"))
      (node (ref "C19") (pin "2") (pinfunction "2_2") (pintype "passive"))
      (node (ref "C2") (pin "2") (pinfunction "2_2") (pintype "passive"))
      (node (ref "C20") (pin "2") (pinfunction "2_2") (pintype "passive"))
      (node (ref "C21") (pin "2") (pinfunction "2_2") (pintype "passive"))
      (node (ref "C22") (pin "2") (pinfunction "2_2") (pintype "passive"))
      (node (ref "C23") (pin "1") (pinfunction "1_1") (pintype "passive"))
      (node (ref "C24") (pin "1") (pinfunction "1_1") (pintype "passive"))
      (node (ref "C25") (pin "2") (pinfunction "2_2") (pintype "passive"))
      (node (ref "C27") (pin "1") (pinfunction "1_1") (pintype "passive"))
      (node (ref "C29") (pin "1") (pinfunction "1_1") (pintype "passive"))
      (node (ref "C3") (pin "2") (pinfunction "2_2") (pintype "passive"))
      (node (ref "C30") (pin "1") (pinfunction "1_1") (pintype "passive"))
      (node (ref "C31") (pin "1") (pinfunction "1_1") (pintype "passive"))
      (node (ref "C32") (pin "1") (pinfunction "1_1") (pintype "passive"))
      (node (ref "C33") (pin "2") (pinfunction "2_2") (pintype "passive"))
      (node (ref "C34") (pin "1") (pinfunction "1_1") (pintype "passive"))
      (node (ref "C37") (pin "1") (pinfunction "1_1") (pintype "passive"))
      (node (ref "C38") (pin "1") (pinfunction "1_1") (pintype "passive"))
      (node (ref "C39") (pin "1") (pinfunction "1_1") (pintype "passive"))
      (node (ref "C4") (pin "2") (pinfunction "2_2") (pintype "passive"))
      (node (ref "C42") (pin "1") (pinfunction "1_1") (pintype "passive"))
      (node (ref "C43") (pin "2") (pinfunction "2_2") (pintype "passive"))
      (node (ref "C5") (pin "2") (pinfunction "2_2") (pintype "passive"))
      (node (ref "C6") (pin "2") (pinfunction "2_2") (pintype "passive"))
      (node (ref "C7") (pin "2") (pinfunction "2_2") (pintype "passive"))
      (node (ref "C8") (pin "2") (pinfunction "2_2") (pintype "passive"))
      (node (ref "C9") (pin "2") (pinfunction "2_2") (pintype "passive"))
      (node (ref "D3") (pin "2") (pinfunction "GND_2") (pintype "bidirectional"))
      (node (ref "D4") (pin "1") (pinfunction "K_1") (pintype "bidirectional"))
      (node (ref "EPD_C1") (pin "1") (pinfunction "1_1") (pintype "passive"))
      (node (ref "EPD_C10") (pin "1") (pinfunction "1_1") (pintype "passive"))
      (node (ref "EPD_C11") (pin "1") (pinfunction "1_1") (pintype "passive"))
      (node (ref "EPD_C12") (pin "1") (pinfunction "1_1") (pintype "passive"))
      (node (ref "EPD_C2") (pin "1") (pinfunction "1_1") (pintype "passive"))
      (node (ref "EPD_C5") (pin "1") (pinfunction "1_1") (pintype "passive"))
      (node (ref "EPD_C6") (pin "1") (pinfunction "1_1") (pintype "passive"))
      (node (ref "EPD_C7") (pin "1") (pinfunction "1_1") (pintype "passive"))
      (node (ref "EPD_C8") (pin "1") (pinfunction "1_1") (pintype "passive"))
      (node (ref "EPD_C9") (pin "1") (pinfunction "1_1") (pintype "passive"))
      (node (ref "IC1") (pin "D2") (pinfunction "GND_D2") (pintype "bidirectional"))
      (node (ref "IC2") (pin "B1") (pinfunction "IN/TRIG_B1") (pintype "bidirectional"))
      (node (ref "IC2") (pin "B3") (pinfunction "GND_B3") (pintype "bidirectional"))
      (node (ref "IC3") (pin "8") (pinfunction "GNDIO_8") (pintype "bidirectional"))
      (node (ref "IC3") (pin "9") (pinfunction "GND_9") (pintype "bidirectional"))
      (node (ref "IC9") (pin "B1") (pinfunction "VSEL_B1") (pintype "bidirectional"))
      (node (ref "IC9") (pin "C1") (pinfunction "AGND_C1") (pintype "bidirectional"))
      (node (ref "IC9") (pin "C2") (pinfunction "PGND_1_C2") (pintype "bidirectional"))
      (node (ref "IC9") (pin "C3") (pinfunction "PGND_2_C3") (pintype "bidirectional"))
      (node (ref "J1") (pin "17") (pinfunction "17_17") (pintype "bidirectional"))
      (node (ref "J1") (pin "8") (pinfunction "8_8") (pintype "bidirectional"))
      (node (ref "J1") (pin "MP1") (pinfunction "MP1_MP1") (pintype "bidirectional"))
      (node (ref "J1") (pin "MP2") (pinfunction "MP2_MP2") (pintype "bidirectional"))
      (node (ref "J2") (pin "3") (pinfunction "3_3") (pintype "bidirectional"))
      (node (ref "J2") (pin "5") (pinfunction "5_5") (pintype "bidirectional"))
      (node (ref "J4") (pin "A12_B1") (pinfunction "GND_A12_B1") (pintype "power_in"))
      (node (ref "J4") (pin "A1_B12") (pinfunction "GND_A1_B12") (pintype "power_in"))
      (node (ref "J4") (pin "SH1") (pinfunction "SHIELD_SH1") (pintype "passive"))
      (node (ref "J4") (pin "SH2") (pinfunction "SHIELD_SH2") (pintype "passive"))
      (node (ref "J4") (pin "SH3") (pinfunction "SHIELD_SH3") (pintype "passive"))
      (node (ref "J4") (pin "SH4") (pinfunction "SHIELD_SH4") (pintype "passive"))
      (node (ref "R1_USB") (pin "1") (pinfunction "1_1") (pintype "bidirectional"))
      (node (ref "R2_EP_DR") (pin "1") (pinfunction "1_1") (pintype "bidirectional"))
      (node (ref "R2_USB") (pin "2") (pinfunction "2_2") (pintype "bidirectional"))
      (node (ref "R3") (pin "1") (pinfunction "1_1") (pintype "bidirectional"))
      (node (ref "R9") (pin "1") (pinfunction "1_1") (pintype "bidirectional"))
      (node (ref "R_TYPE_SEL") (pin "1") (pinfunction "1_1") (pintype "bidirectional"))
      (node (ref "SJ1") (pin "1") (pinfunction "1_1") (pintype "passive"))
      (node (ref "SW_DN") (pin "1") (pinfunction "1_1") (pintype "passive"))
      (node (ref "SW_ENT") (pin "1") (pinfunction "1_1") (pintype "passive"))
      (node (ref "SW_UP") (pin "1") (pinfunction "1_1") (pintype "passive"))
      (node (ref "TP_BAT_GND") (pin "TP") (pinfunction "TP_TP") (pintype "input"))
      (node (ref "TP_GND") (pin "TP") (pinfunction "TP_TP") (pintype "input"))
      (node (ref "U1") (pin "P$74") (pinfunction "VSS_PAD_P$74") (pintype "bidirectional"))
      (node (ref "U1") (pin "P$75") (pinfunction "VSS_PAD_P$75") (pintype "bidirectional"))
      (node (ref "U1") (pin "P$76") (pinfunction "VSS_PAD_P$76") (pintype "bidirectional"))
      (node (ref "U1") (pin "P$77") (pinfunction "VSS_PAD_P$77") (pintype "bidirectional"))
      (node (ref "U1") (pin "P$78") (pinfunction "VSS_PAD_P$78") (pintype "bidirectional"))
      (node (ref "U1") (pin "P$79") (pinfunction "VSS_PAD_P$79") (pintype "bidirectional"))
      (node (ref "U1") (pin "P$80") (pinfunction "VSS_PAD_P$80") (pintype "bidirectional"))
      (node (ref "U1") (pin "P$81") (pinfunction "VSS_PAD_P$81") (pintype "bidirectional"))
      (node (ref "U1") (pin "P$82") (pinfunction "VSS_PAD_P$82") (pintype "bidirectional"))
      (node (ref "U1") (pin "P$83") (pinfunction "VSS_PAD_P$83") (pintype "bidirectional"))
      (node (ref "U1") (pin "P$84") (pinfunction "VSS_PAD_P$84") (pintype "bidirectional"))
      (node (ref "U1") (pin "P$85") (pinfunction "VSS_PAD_P$85") (pintype "bidirectional"))
      (node (ref "U1") (pin "P$86") (pinfunction "VSS_PAD_P$86") (pintype "bidirectional"))
      (node (ref "U1") (pin "P$87") (pinfunction "VSS_PAD_P$87") (pintype "bidirectional"))
      (node (ref "U1") (pin "P$88") (pinfunction "VSS_PAD_P$88") (pintype "bidirectional"))
      (node (ref "U1") (pin "P$89") (pinfunction "VSS_PAD_P$89") (pintype "bidirectional"))
      (node (ref "U1") (pin "P$90") (pinfunction "VSS_PAD_P$90") (pintype "bidirectional"))
      (node (ref "U1") (pin "P$B7") (pinfunction "VSS_P$B7") (pintype "power_in"))
      (node (ref "U1") (pin "P$F23") (pinfunction "VSS_PA_P$F23") (pintype "bidirectional"))
      (node (ref "U3") (pin "1") (pinfunction "CTG_1") (pintype "power_in"))
      (node (ref "U3") (pin "4") (pinfunction "GND_4") (pintype "power_in"))
      (node (ref "U3") (pin "6") (pinfunction "QSTRT_6") (pintype "input"))
      (node (ref "U3") (pin "9") (pinfunction "EP_9") (pintype "power_in"))
      (node (ref "X1") (pin "2") (pinfunction "2_2") (pintype "passive"))
      (node (ref "X1") (pin "4") (pinfunction "4_4") (pintype "passive"))
    )
    (net (code "19") (name "HAPTIC_EN") (class "Default")
      (node (ref "IC2") (pin "A1") (pinfunction "EN_A1") (pintype "bidirectional"))
      (node (ref "U1") (pin "P$U1") (pinfunction "P0.12_P$U1") (pintype "bidirectional"))
    )
    (net (code "20") (name "IMU_INT1") (class "Default")
      (node (ref "IC3") (pin "5") (pinfunction "INT1_5") (pintype "bidirectional"))
      (node (ref "U1") (pin "P$N1") (pinfunction "P0.08_P$N1") (pintype "bidirectional"))
    )
    (net (code "21") (name "IMU_INT2") (class "Default")
      (node (ref "IC3") (pin "6") (pinfunction "INT2_6") (pintype "bidirectional"))
      (node (ref "U1") (pin "P$P2") (pinfunction "P1.08_P$P2") (pintype "bidirectional"))
    )
    (net (code "22") (name "LX1") (class "Default")
      (node (ref "IC9") (pin "B2") (pinfunction "SW1_1_B2") (pintype "bidirectional"))
      (node (ref "IC9") (pin "B3") (pinfunction "SW1_2_B3") (pintype "bidirectional"))
      (node (ref "L7") (pin "1") (pinfunction "1_1") (pintype "bidirectional"))
    )
    (net (code "23") (name "LX2") (class "Default")
      (node (ref "IC9") (pin "D2") (pinfunction "SW2_1_D2") (pintype "bidirectional"))
      (node (ref "IC9") (pin "D3") (pinfunction "SW2_2_D3") (pintype "bidirectional"))
      (node (ref "L7") (pin "2") (pinfunction "2_2") (pintype "bidirectional"))
    )
    (net (code "24") (name "MOSI") (class "Default")
      (node (ref "J1") (pin "14") (pinfunction "14_14") (pintype "bidirectional"))
      (node (ref "U1") (pin "P$B13") (pinfunction "P0.03/AIN1_P$B13") (pintype "bidirectional"))
    )
    (net (code "25") (name "Net-(ANT1-FEED)") (class "Default")
      (node (ref "ANT1") (pin "1") (pinfunction "FEED_1") (pintype "input"))
      (node (ref "C22") (pin "1") (pinfunction "1_1") (pintype "passive"))
      (node (ref "C4") (pin "1") (pinfunction "1_1") (pintype "passive"))
      (node (ref "L1") (pin "2") (pinfunction "2_2") (pintype "passive"))
    )
    (net (code "26") (name "Net-(D2-K)") (class "Default")
      (node (ref "C2-EP-DR") (pin "1") (pinfunction "1_1") (pintype "passive"))
      (node (ref "D2") (pin "1") (pinfunction "K_1") (pintype "bidirectional"))
      (node (ref "D4") (pin "2") (pinfunction "A_2") (pintype "bidirectional"))
    )
    (net (code "27") (name "Net-(D5-A)") (class "Default")
      (node (ref "C2-EP-DR") (pin "2") (pinfunction "2_2") (pintype "passive"))
      (node (ref "D5") (pin "2") (pinfunction "A_2") (pintype "bidirectional"))
      (node (ref "L5") (pin "1") (pinfunction "1_1") (pintype "passive"))
      (node (ref "Q3") (pin "3") (pinfunction "D_3") (pintype "bidirectional"))
    )
    (net (code "28") (name "Net-(EPD_C1-Pad2)") (class "Default")
      (node (ref "EPD_C1") (pin "2") (pinfunction "2_2") (pintype "passive"))
      (node (ref "J1") (pin "5") (pinfunction "5_5") (pintype "bidirectional"))
    )
    (net (code "29") (name "Net-(EPD_C2-Pad2)") (class "Default")
      (node (ref "EPD_C2") (pin "2") (pinfunction "2_2") (pintype "passive"))
      (node (ref "J1") (pin "4") (pinfunction "4_4") (pintype "bidirectional"))
    )
    (net (code "30") (name "Net-(EPD_C6-Pad2)") (class "Default")
      (node (ref "EPD_C6") (pin "2") (pinfunction "2_2") (pintype "passive"))
      (node (ref "J1") (pin "18") (pinfunction "18_18") (pintype "bidirectional"))
    )
    (net (code "31") (name "Net-(EPD_C7-Pad2)") (class "Default")
      (node (ref "EPD_C7") (pin "2") (pinfunction "2_2") (pintype "passive"))
      (node (ref "J1") (pin "19") (pinfunction "19_19") (pintype "bidirectional"))
    )
    (net (code "32") (name "Net-(EPD_C8-Pad2)") (class "Default")
      (node (ref "EPD_C8") (pin "2") (pinfunction "2_2") (pintype "passive"))
      (node (ref "J1") (pin "20") (pinfunction "20_20") (pintype "bidirectional"))
    )
    (net (code "33") (name "Net-(EPD_C10-Pad2)") (class "Default")
      (node (ref "EPD_C10") (pin "2") (pinfunction "2_2") (pintype "passive"))
      (node (ref "J1") (pin "22") (pinfunction "22_22") (pintype "bidirectional"))
    )
    (net (code "34") (name "Net-(EPD_C12-Pad2)") (class "Default")
      (node (ref "EPD_C12") (pin "2") (pinfunction "2_2") (pintype "passive"))
      (node (ref "J1") (pin "24") (pinfunction "24_24") (pintype "bidirectional"))
    )
    (net (code "35") (name "Net-(IC1-TS{slash}MR)") (class "Default")
      (node (ref "IC1") (pin "D1") (pinfunction "TS/MR_D1") (pintype "bidirectional"))
      (node (ref "R9") (pin "2") (pinfunction "2_2") (pintype "bidirectional"))
    )
    (net (code "36") (name "Net-(IC2-REG)") (class "Default")
      (node (ref "C32") (pin "2") (pinfunction "2_2") (pintype "passive"))
      (node (ref "IC2") (pin "A2") (pinfunction "REG_A2") (pintype "bidirectional"))
    )
    (net (code "37") (name "Net-(IC3-SDO)") (class "Default")
      (node (ref "IC3") (pin "1") (pinfunction "SDO_1") (pintype "bidirectional"))
      (node (ref "R3") (pin "2") (pinfunction "2_2") (pintype "bidirectional"))
    )
    (net (code "38") (name "Net-(IC9-SCL)") (class "Default")
      (node (ref "IC9") (pin "D1") (pinfunction "SCL_D1") (pintype "bidirectional"))
      (node (ref "R4") (pin "2") (pinfunction "2_2") (pintype "bidirectional"))
    )
    (net (code "39") (name "Net-(IC9-SDA)") (class "Default")
      (node (ref "IC9") (pin "E1") (pinfunction "SDA_E1") (pintype "bidirectional"))
      (node (ref "R2") (pin "2") (pinfunction "2_2") (pintype "bidirectional"))
    )
    (net (code "40") (name "Net-(J4-CC1)") (class "Default")
      (node (ref "J4") (pin "A5") (pinfunction "CC1_A5") (pintype "bidirectional"))
      (node (ref "R1_USB") (pin "2") (pinfunction "2_2") (pintype "bidirectional"))
    )
    (net (code "41") (name "Net-(J4-CC2)") (class "Default")
      (node (ref "J4") (pin "B5") (pinfunction "CC2_B5") (pintype "bidirectional"))
      (node (ref "R2_USB") (pin "1") (pinfunction "1_1") (pintype "bidirectional"))
    )
    (net (code "42") (name "Net-(L2-Pad2)") (class "Default")
      (node (ref "L2") (pin "2") (pinfunction "2_2") (pintype "passive"))
      (node (ref "L3") (pin "1") (pinfunction "1_1") (pintype "passive"))
    )
    (net (code "43") (name "Net-(R1_EP_DR-Pad1)") (class "Default")
      (node (ref "R1_EP_DR") (pin "1") (pinfunction "1_1") (pintype "bidirectional"))
      (node (ref "R_TYPE_SEL") (pin "2") (pinfunction "2_2") (pintype "bidirectional"))
      (node (ref "SJ1") (pin "2") (pinfunction "2_2") (pintype "passive"))
    )
    (net (code "44") (name "Net-(U1-ANT)") (class "Default")
      (node (ref "C3") (pin "1") (pinfunction "1_1") (pintype "passive"))
      (node (ref "L1") (pin "1") (pinfunction "1_1") (pintype "passive"))
      (node (ref "U1") (pin "P$H23") (pinfunction "ANT_P$H23") (pintype "bidirectional"))
    )
    (net (code "45") (name "Net-(U1-DCC)") (class "Default")
      (node (ref "L2") (pin "1") (pinfunction "1_1") (pintype "passive"))
      (node (ref "U1") (pin "P$B3") (pinfunction "DCC_P$B3") (pintype "output"))
    )
    (net (code "46") (name "Net-(U1-DEC2)") (class "Default")
      (node (ref "C13") (pin "1") (pinfunction "1_1") (pintype "passive"))
      (node (ref "U1") (pin "P$A18") (pinfunction "DEC2_P$A18") (pintype "bidirectional"))
    )
    (net (code "47") (name "Net-(U1-DEC3V3)") (class "Default")
      (node (ref "C20") (pin "1") (pinfunction "1_1") (pintype "passive"))
      (node (ref "U1") (pin "P$AC5") (pinfunction "DEC3V3_P$AC5") (pintype "bidirectional"))
    )
    (net (code "48") (name "Net-(U1-DEC5)") (class "Default")
      (node (ref "C9") (pin "1") (pinfunction "1_1") (pintype "passive"))
      (node (ref "U1") (pin "P$N24") (pinfunction "DEC5_P$N24") (pintype "bidirectional"))
    )
    (net (code "49") (name "Net-(U1-XC1)") (class "Default")
      (node (ref "C1") (pin "1") (pinfunction "1_1") (pintype "passive"))
      (node (ref "U1") (pin "P$B24") (pinfunction "XC1_P$B24") (pintype "input"))
      (node (ref "X1") (pin "1") (pinfunction "1_1") (pintype "passive"))
    )
    (net (code "50") (name "Net-(U1-XC2)") (class "Default")
      (node (ref "C2") (pin "1") (pinfunction "1_1") (pintype "passive"))
      (node (ref "U1") (pin "P$A23") (pinfunction "XC2_P$A23") (pintype "output"))
      (node (ref "X1") (pin "3") (pinfunction "3_3") (pintype "passive"))
    )
    (net (code "51") (name "OUT+") (class "Default")
      (node (ref "IC2") (pin "A3") (pinfunction "OUT+_A3") (pintype "bidirectional"))
      (node (ref "TP_OP") (pin "TP") (pinfunction "TP_TP") (pintype "input"))
    )
    (net (code "52") (name "OUT-") (class "Default")
      (node (ref "IC2") (pin "C3") (pinfunction "OUT-_C3") (pintype "bidirectional"))
      (node (ref "TP_ON") (pin "TP") (pinfunction "TP_TP") (pintype "input"))
    )
    (net (code "53") (name "P0.04") (class "Default")
      (node (ref "U1") (pin "P$J1") (pinfunction "P0.04/AIN2_P$J1") (pintype "bidirectional"))
    )
    (net (code "54") (name "P0.09") (class "Default")
      (node (ref "U1") (pin "P$L24") (pinfunction "P0.09/NFC1_P$L24") (pintype "bidirectional"))
    )
    (net (code "55") (name "P0.13") (class "Default")
      (node (ref "C30") (pin "2") (pinfunction "2_2") (pintype "passive"))
      (node (ref "R5") (pin "1") (pinfunction "1_1") (pintype "bidirectional"))
      (node (ref "SW_UP") (pin "2") (pinfunction "2_2") (pintype "passive"))
    )
    (net (code "56") (name "P0.14") (class "Default")
      (node (ref "C31") (pin "2") (pinfunction "2_2") (pintype "passive"))
      (node (ref "R8") (pin "1") (pinfunction "1_1") (pintype "bidirectional"))
      (node (ref "SW_ENT") (pin "2") (pinfunction "2_2") (pintype "passive"))
    )
    (net (code "57") (name "P0.19") (class "Default")
      (node (ref "U1") (pin "P$AC15") (pinfunction "P0.19_P$AC15") (pintype "bidirectional"))
    )
    (net (code "58") (name "P0.20") (class "Default")
      (node (ref "U1") (pin "P$AD16") (pinfunction "P0.20_P$AD16") (pintype "bidirectional"))
    )
    (net (code "59") (name "P0.21") (class "Default")
      (node (ref "U1") (pin "P$AC17") (pinfunction "P0.21_P$AC17") (pintype "bidirectional"))
    )
    (net (code "60") (name "P0.22") (class "Default")
      (node (ref "U1") (pin "P$AD18") (pinfunction "P0.22_P$AD18") (pintype "bidirectional"))
    )
    (net (code "61") (name "P0.23") (class "Default")
      (node (ref "U1") (pin "P$AC19") (pinfunction "P0.23_P$AC19") (pintype "bidirectional"))
    )
    (net (code "62") (name "P0.24") (class "Default")
      (node (ref "U1") (pin "P$AD20") (pinfunction "P0.24_P$AD20") (pintype "bidirectional"))
    )
    (net (code "63") (name "P0.25") (class "Default")
      (node (ref "U1") (pin "P$AC21") (pinfunction "P0.25_P$AC21") (pintype "bidirectional"))
    )
    (net (code "64") (name "P0.26") (class "Default")
      (node (ref "U1") (pin "P$G1") (pinfunction "P0.26_P$G1") (pintype "bidirectional"))
    )
    (net (code "65") (name "P0.27") (class "Default")
      (node (ref "U1") (pin "P$H2") (pinfunction "P0.27_P$H2") (pintype "bidirectional"))
    )
    (net (code "66") (name "P0.28") (class "Default")
      (node (ref "U1") (pin "P$B11") (pinfunction "P0.28/AIN4_P$B11") (pintype "bidirectional"))
    )
    (net (code "67") (name "P0.29") (class "Default")
      (node (ref "U1") (pin "P$A10") (pinfunction "P0.29/AIN5_P$A10") (pintype "bidirectional"))
    )
    (net (code "68") (name "P0.30") (class "Default")
      (node (ref "U1") (pin "P$B9") (pinfunction "P0.30/AIN6_P$B9") (pintype "bidirectional"))
    )
    (net (code "69") (name "P0.31") (class "Default")
      (node (ref "U1") (pin "P$A8") (pinfunction "P0.31/AIN7_P$A8") (pintype "bidirectional"))
    )
    (net (code "70") (name "P1.01") (class "Default")
      (node (ref "Q1") (pin "1") (pinfunction "G_1") (pintype "bidirectional"))
      (node (ref "R_PWR_EPD") (pin "1") (pinfunction "1_1") (pintype "bidirectional"))
      (node (ref "U1") (pin "P$Y23") (pinfunction "P1.01_P$Y23") (pintype "bidirectional"))
    )
    (net (code "71") (name "P1.02") (class "Default")
      (node (ref "C29") (pin "2") (pinfunction "2_2") (pintype "passive"))
      (node (ref "R7") (pin "1") (pinfunction "1_1") (pintype "bidirectional"))
      (node (ref "SW_DN") (pin "2") (pinfunction "2_2") (pintype "passive"))
      (node (ref "U1") (pin "P$W24") (pinfunction "P1.02_P$W24") (pintype "bidirectional"))
    )
    (net (code "72") (name "P1.03") (class "Default")
      (node (ref "U1") (pin "P$V23") (pinfunction "P1.03_P$V23") (pintype "bidirectional"))
    )
    (net (code "73") (name "P1.04") (class "Default")
      (node (ref "U1") (pin "P$U24") (pinfunction "P1.04_P$U24") (pintype "bidirectional"))
    )
    (net (code "74") (name "P1.05") (class "Default")
      (node (ref "U1") (pin "P$T23") (pinfunction "P1.05_P$T23") (pintype "bidirectional"))
    )
    (net (code "75") (name "P1.06") (class "Default")
      (node (ref "U1") (pin "P$R24") (pinfunction "P1.06_P$R24") (pintype "bidirectional"))
    )
    (net (code "76") (name "P1.07") (class "Default")
      (node (ref "U1") (pin "P$P23") (pinfunction "P1.07_P$P23") (pintype "bidirectional"))
    )
    (net (code "77") (name "P1.09") (class "Default")
      (node (ref "U1") (pin "P$R1") (pinfunction "P1.09_P$R1") (pintype "bidirectional"))
    )
    (net (code "78") (name "P1.10") (class "Default")
      (node (ref "U1") (pin "P$A20") (pinfunction "P1.10_P$A20") (pintype "bidirectional"))
    )
    (net (code "79") (name "P1.11") (class "Default")
      (node (ref "U1") (pin "P$B19") (pinfunction "P1.11_P$B19") (pintype "bidirectional"))
    )
    (net (code "80") (name "P1.12") (class "Default")
      (node (ref "U1") (pin "P$B17") (pinfunction "P1.12_P$B17") (pintype "bidirectional"))
    )
    (net (code "81") (name "P1.13") (class "Default")
      (node (ref "U1") (pin "P$A16") (pinfunction "P1.13_P$A16") (pintype "bidirectional"))
    )
    (net (code "82") (name "P1.14") (class "Default")
      (node (ref "U1") (pin "P$B15") (pinfunction "P1.14_P$B15") (pintype "bidirectional"))
    )
    (net (code "83") (name "P1.15") (class "Default")
      (node (ref "U1") (pin "P$A14") (pinfunction "P1.15_P$A14") (pintype "bidirectional"))
    )
    (net (code "84") (name "PMIC_INT") (class "Default")
      (node (ref "IC1") (pin "A1") (pinfunction "~{INT}_A1") (pintype "bidirectional"))
      (node (ref "U1") (pin "P$T2") (pinfunction "P0.11_P$T2") (pintype "bidirectional"))
    )
    (net (code "85") (name "PO.13") (class "Default")
      (node (ref "U1") (pin "P$AD8") (pinfunction "P0.13_P$AD8") (pintype "bidirectional"))
    )
    (net (code "86") (name "PO.14") (class "Default")
      (node (ref "U1") (pin "P$AC9") (pinfunction "P0.14_P$AC9") (pintype "bidirectional"))
    )
    (net (code "87") (name "PREVGH") (class "Default")
      (node (ref "D5") (pin "1") (pinfunction "K_1") (pintype "bidirectional"))
      (node (ref "EPD_C9") (pin "2") (pinfunction "2_2") (pintype "passive"))
      (node (ref "J1") (pin "21") (pinfunction "21_21") (pintype "bidirectional"))
    )
    (net (code "88") (name "PREVGL") (class "Default")
      (node (ref "D2") (pin "2") (pinfunction "A_2") (pintype "bidirectional"))
      (node (ref "EPD_C11") (pin "2") (pinfunction "2_2") (pintype "passive"))
      (node (ref "J1") (pin "23") (pinfunction "23_23") (pintype "bidirectional"))
    )
    (net (code "89") (name "RESE") (class "Default")
      (node (ref "J1") (pin "3") (pinfunction "3_3") (pintype "bidirectional"))
      (node (ref "Q3") (pin "2") (pinfunction "S_2") (pintype "bidirectional"))
      (node (ref "R1_EP_DR") (pin "2") (pinfunction "2_2") (pintype "bidirectional"))
    )
    (net (code "90") (name "RESET") (class "Default")
      (node (ref "J2") (pin "6") (pinfunction "6_6") (pintype "bidirectional"))
      (node (ref "TP_RESET") (pin "TP") (pinfunction "TP_TP") (pintype "input"))
      (node (ref "U1") (pin "P$AC13") (pinfunction "P0.18/RESET_P$AC13") (pintype "bidirectional"))
    )
    (net (code "91") (name "SCK") (class "Default")
      (node (ref "J1") (pin "13") (pinfunction "13_13") (pintype "bidirectional"))
      (node (ref "U1") (pin "P$A12") (pinfunction "P0.02/AIN0_P$A12") (pintype "bidirectional"))
    )
    (net (code "92") (name "SCL") (class "Default")
      (node (ref "IC1") (pin "B1") (pinfunction "SCL_B1") (pintype "bidirectional"))
      (node (ref "IC2") (pin "C1") (pinfunction "SCL_C1") (pintype "bidirectional"))
      (node (ref "IC3") (pin "12") (pinfunction "SCX_12") (pintype "bidirectional"))
      (node (ref "R17") (pin "2") (pinfunction "2_2") (pintype "bidirectional"))
      (node (ref "R4") (pin "1") (pinfunction "1_1") (pintype "bidirectional"))
      (node (ref "TP_SCL") (pin "TP") (pinfunction "TP_TP") (pintype "input"))
      (node (ref "U1") (pin "P$M2") (pinfunction "P0.07_P$M2") (pintype "bidirectional"))
      (node (ref "U3") (pin "7") (pinfunction "SCL_7") (pintype "input"))
    )
    (net (code "93") (name "SDA") (class "Default")
      (node (ref "IC1") (pin "C1") (pinfunction "SDA_C1") (pintype "bidirectional"))
      (node (ref "IC2") (pin "B2") (pinfunction "SDA_B2") (pintype "bidirectional"))
      (node (ref "IC3") (pin "2") (pinfunction "SDX_2") (pintype "bidirectional"))
      (node (ref "R18") (pin "2") (pinfunction "2_2") (pintype "bidirectional"))
      (node (ref "R2") (pin "1") (pinfunction "1_1") (pintype "bidirectional"))
      (node (ref "TP_SDA") (pin "TP") (pinfunction "TP_TP") (pintype "input"))
      (node (ref "U1") (pin "P$L1") (pinfunction "P0.06_P$L1") (pintype "bidirectional"))
      (node (ref "U3") (pin "8") (pinfunction "SDA_8") (pintype "bidirectional"))
    )
    (net (code "94") (name "SWDCLK") (class "Default")
      (node (ref "J2") (pin "4") (pinfunction "4_4") (pintype "bidirectional"))
      (node (ref "TP_SWDCLK") (pin "TP") (pinfunction "TP_TP") (pintype "input"))
      (node (ref "U1") (pin "P$AA24") (pinfunction "SWDCLK_P$AA24") (pintype "input"))
    )
    (net (code "95") (name "SWDIO") (class "Default")
      (node (ref "J2") (pin "2") (pinfunction "2_2") (pintype "bidirectional"))
      (node (ref "TP_SWDIO") (pin "TP") (pinfunction "TP_TP") (pintype "input"))
      (node (ref "U1") (pin "P$AC24") (pinfunction "SWDIO_P$AC24") (pintype "bidirectional"))
    )
    (net (code "96") (name "SWO") (class "Default")
      (node (ref "TP_SWO") (pin "TP") (pinfunction "TP_TP") (pintype "input"))
      (node (ref "U1") (pin "P$AD22") (pinfunction "P1.00_P$AD22") (pintype "bidirectional"))
    )
    (net (code "97") (name "VBAT") (class "Default")
      (node (ref "C27") (pin "2") (pinfunction "2_2") (pintype "passive"))
      (node (ref "C37") (pin "2") (pinfunction "2_2") (pintype "passive"))
      (node (ref "IC1") (pin "C2") (pinfunction "BAT_C2") (pintype "bidirectional"))
      (node (ref "TP_VBAT") (pin "TP") (pinfunction "TP_TP") (pintype "input"))
      (node (ref "U3") (pin "2") (pinfunction "CELL_2") (pintype "power_in"))
      (node (ref "U3") (pin "3") (pinfunction "VDD_3") (pintype "power_in"))
    )
    (net (code "98") (name "VBUS") (class "Default")
      (node (ref "C21") (pin "1") (pinfunction "1_1") (pintype "passive"))
      (node (ref "C38") (pin "2") (pinfunction "2_2") (pintype "passive"))
      (node (ref "C42") (pin "2") (pinfunction "2_2") (pintype "passive"))
      (node (ref "C43") (pin "1") (pinfunction "1_1") (pintype "passive"))
      (node (ref "D3") (pin "5") (pinfunction "VBUS_5") (pintype "bidirectional"))
      (node (ref "IC1") (pin "A2") (pinfunction "IN_A2") (pintype "bidirectional"))
      (node (ref "J4") (pin "A4_B9") (pinfunction "VBUS_A4_B9") (pintype "power_in"))
      (node (ref "J4") (pin "A9_B4") (pinfunction "VBUS_A9_B4") (pintype "power_in"))
      (node (ref "U1") (pin "P$AD2") (pinfunction "VBUS_P$AD2") (pintype "power_in"))
    )
    (net (code "99") (name "VREG") (class "Default")
      (node (ref "C23") (pin "2") (pinfunction "2_2") (pintype "passive"))
      (node (ref "C24") (pin "2") (pinfunction "2_2") (pintype "passive"))
      (node (ref "C39") (pin "2") (pinfunction "2_2") (pintype "passive"))
      (node (ref "IC1") (pin "B2") (pinfunction "SYS_B2") (pintype "bidirectional"))
      (node (ref "IC9") (pin "A1") (pinfunction "EN_A1") (pintype "bidirectional"))
      (node (ref "IC9") (pin "A2") (pinfunction "VIN_1_A2") (pintype "bidirectional"))
      (node (ref "IC9") (pin "A3") (pinfunction "VIN_2_A3") (pintype "bidirectional"))
      (node (ref "TP_VREG") (pin "TP") (pinfunction "TP_TP") (pintype "input"))
    )
    (net (code "100") (name "unconnected-(ANT1-NC-Pad2)") (class "Default")
      (node (ref "ANT1") (pin "2") (pinfunction "NC_2") (pintype "no_connect"))
    )
    (net (code "101") (name "unconnected-(IC3-ASCL-Pad11)") (class "Default")
      (node (ref "IC3") (pin "11") (pinfunction "ASCL_11") (pintype "bidirectional"))
    )
    (net (code "102") (name "unconnected-(IC3-ASDA-Pad4)") (class "Default")
      (node (ref "IC3") (pin "4") (pinfunction "ASDA_4") (pintype "bidirectional"))
    )
    (net (code "103") (name "unconnected-(J1-Pad1)") (class "Default")
      (node (ref "J1") (pin "1") (pinfunction "1_1") (pintype "bidirectional"))
    )
    (net (code "104") (name "unconnected-(J1-Pad6)") (class "Default")
      (node (ref "J1") (pin "6") (pinfunction "6_6") (pintype "bidirectional"))
    )
    (net (code "105") (name "unconnected-(J1-Pad7)") (class "Default")
      (node (ref "J1") (pin "7") (pinfunction "7_7") (pintype "bidirectional"))
    )
    (net (code "106") (name "unconnected-(J4-SBU1-PadA8)") (class "Default")
      (node (ref "J4") (pin "A8") (pinfunction "SBU1_A8") (pintype "bidirectional"))
    )
    (net (code "107") (name "unconnected-(J4-SBU2-PadB8)") (class "Default")
      (node (ref "J4") (pin "B8") (pinfunction "SBU2_B8") (pintype "bidirectional"))
    )
    (net (code "108") (name "unconnected-(U1-DCCH-PadP$AB2)") (class "Default")
      (node (ref "U1") (pin "P$AB2") (pinfunction "DCCH_P$AB2") (pintype "bidirectional"))
    )
  )
)
